# untitled.net
KiCad netlist of a schematic drawn in EAGLE
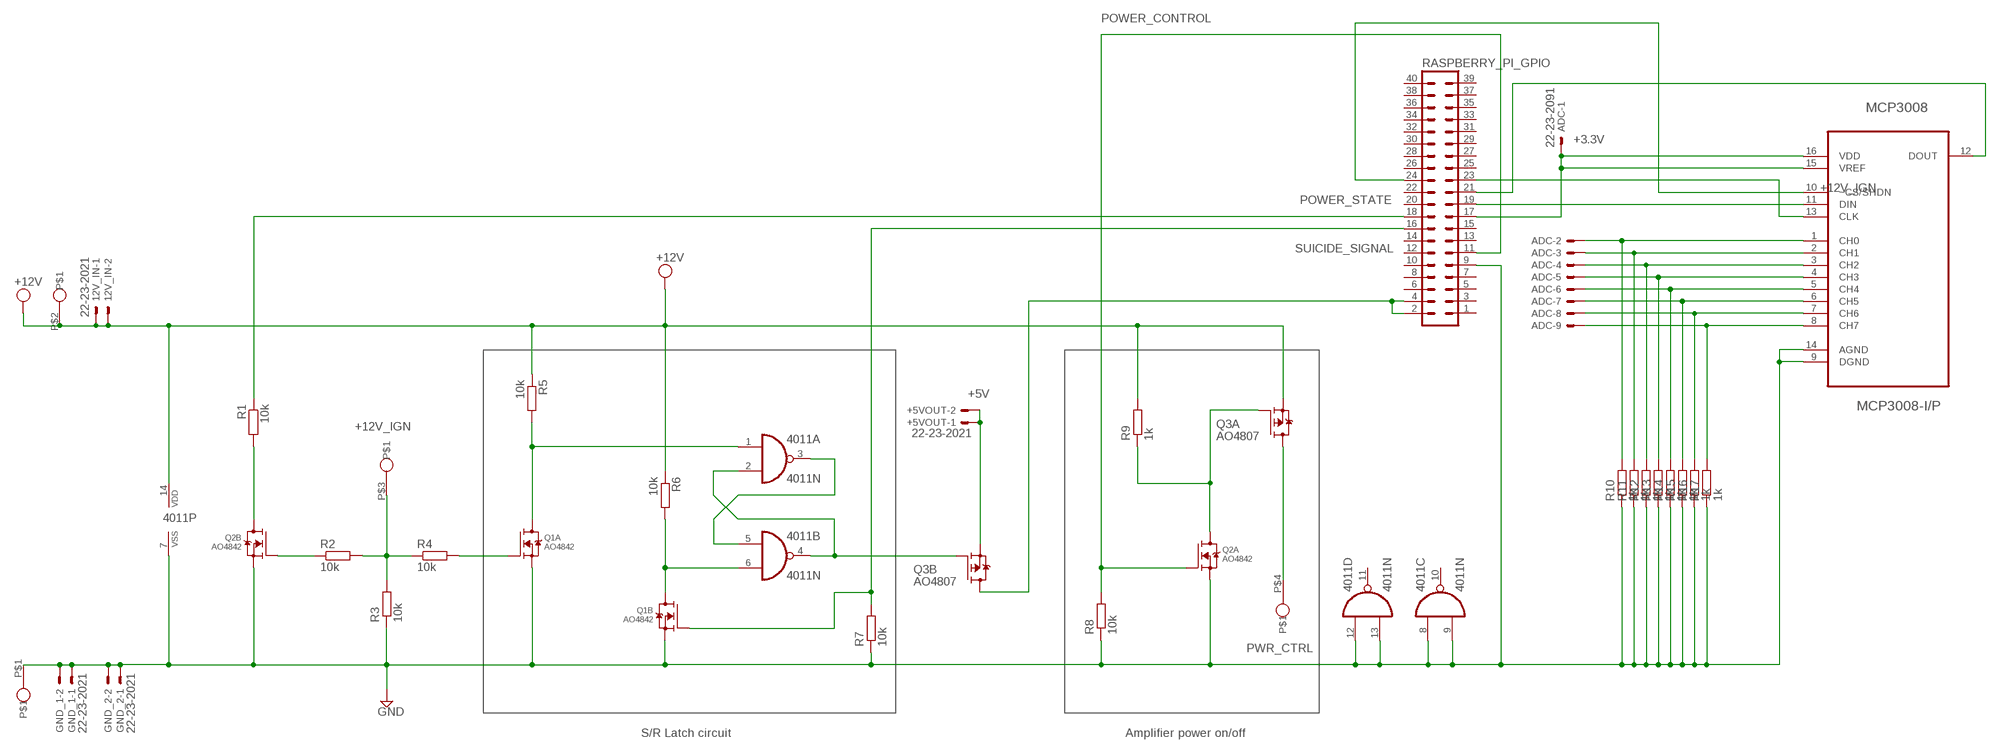
[diagram p0: schematic, sheet 1]

(export (version "E")
  (design (tool "Eeschema 10.0.6"))
  (components
    (comp (ref "+5VOUT")
      (value "22-23-2021")
      (footprint "eagle-import:22-23-2021")
      (fields (field (name "MF") "MOLEX"))
      (libsource (lib "eagle-import") (part "22-23-2021"))
    )
    (comp (ref "12V_IN")
      (value "22-23-2021")
      (footprint "eagle-import:22-23-2021")
      (fields (field (name "MF") "MOLEX"))
      (libsource (lib "eagle-import") (part "22-23-2021"))
    )
    (comp (ref "4011")
      (value "4011N")
      (footprint "eagle-import:DIL14")
      (libsource (lib "eagle-import") (part "4011N"))
    )
    (comp (ref "ADC")
      (value "22-23-2091")
      (footprint "eagle-import:22-23-2091")
      (fields (field (name "MF") "MOLEX"))
      (libsource (lib "eagle-import") (part "22-23-2091"))
    )
    (comp (ref "EXT")
      (value "MKDS3")
      (footprint "eagle-import:MKDS3")
      (libsource (lib "eagle-import") (part "MKDS3"))
    )
    (comp (ref "GND_1")
      (value "22-23-2021")
      (footprint "eagle-import:22-23-2021")
      (fields (field (name "MF") "MOLEX"))
      (libsource (lib "eagle-import") (part "22-23-2021"))
    )
    (comp (ref "GND_2")
      (value "22-23-2021")
      (footprint "eagle-import:22-23-2021")
      (fields (field (name "MF") "MOLEX"))
      (libsource (lib "eagle-import") (part "22-23-2021"))
    )
    (comp (ref "MCP3008")
      (value "MCP3008-I/P")
      (footprint "eagle-import:DIP254P762X432-16")
      (libsource (lib "eagle-import") (part "MCP3008-I/P"))
    )
    (comp (ref "Q1")
      (value "AO4842")
      (footprint "eagle-import:8-SOIC")
      (libsource (lib "eagle-import") (part "AO4842"))
    )
    (comp (ref "Q2")
      (value "AO4842")
      (footprint "eagle-import:8-SOIC")
      (libsource (lib "eagle-import") (part "AO4842"))
    )
    (comp (ref "Q3")
      (value "AO4807")
      (footprint "eagle-import:8-SOIC")
      (libsource (lib "eagle-import") (part "AO4807"))
    )
    (comp (ref "R1")
      (value "10k")
      (footprint "eagle-import:0207_10")
      (libsource (lib "eagle-import") (part "R-EU_0207/10"))
    )
    (comp (ref "R2")
      (value "10k")
      (footprint "eagle-import:0207_10")
      (libsource (lib "eagle-import") (part "R-EU_0207/10"))
    )
    (comp (ref "R3")
      (value "10k")
      (footprint "eagle-import:0207_10")
      (libsource (lib "eagle-import") (part "R-EU_0207/10"))
    )
    (comp (ref "R4")
      (value "10k")
      (footprint "eagle-import:0207_10")
      (libsource (lib "eagle-import") (part "R-EU_0207/10"))
    )
    (comp (ref "R5")
      (value "10k")
      (footprint "eagle-import:0207_10")
      (libsource (lib "eagle-import") (part "R-EU_0207/10"))
    )
    (comp (ref "R6")
      (value "10k")
      (footprint "eagle-import:0207_10")
      (libsource (lib "eagle-import") (part "R-EU_0207/10"))
    )
    (comp (ref "R7")
      (value "10k")
      (footprint "eagle-import:0207_10")
      (libsource (lib "eagle-import") (part "R-EU_0207/10"))
    )
    (comp (ref "R8")
      (value "10k")
      (footprint "eagle-import:0207_10")
      (libsource (lib "eagle-import") (part "R-EU_0207/10"))
    )
    (comp (ref "R9")
      (value "1k")
      (footprint "eagle-import:0207_10")
      (libsource (lib "eagle-import") (part "R-EU_0207/10"))
    )
    (comp (ref "R10")
      (value "1k")
      (footprint "eagle-import:0207_10")
      (libsource (lib "eagle-import") (part "R-EU_0207/10"))
    )
    (comp (ref "R11")
      (value "1k")
      (footprint "eagle-import:0207_10")
      (libsource (lib "eagle-import") (part "R-EU_0207/10"))
    )
    (comp (ref "R12")
      (value "1k")
      (footprint "eagle-import:0207_10")
      (libsource (lib "eagle-import") (part "R-EU_0207/10"))
    )
    (comp (ref "R13")
      (value "1k")
      (footprint "eagle-import:0207_10")
      (libsource (lib "eagle-import") (part "R-EU_0207/10"))
    )
    (comp (ref "R14")
      (value "1k")
      (footprint "eagle-import:0207_10")
      (libsource (lib "eagle-import") (part "R-EU_0207/10"))
    )
    (comp (ref "R15")
      (value "1k")
      (footprint "eagle-import:0207_10")
      (libsource (lib "eagle-import") (part "R-EU_0207/10"))
    )
    (comp (ref "R16")
      (value "1k")
      (footprint "eagle-import:0207_10")
      (libsource (lib "eagle-import") (part "R-EU_0207/10"))
    )
    (comp (ref "R17")
      (value "1k")
      (footprint "eagle-import:0207_10")
      (libsource (lib "eagle-import") (part "R-EU_0207/10"))
    )
    (comp (ref "RASPBERRY_PI_GPIO")
      (value "MA20-2")
      (footprint "eagle-import:MA20-2")
      (libsource (lib "eagle-import") (part "MA20-2"))
    )
  )
  (nets
    (net (code "1") (name "+12V") (class "Default")
      (node (ref "12V_IN") (pin "1") (pinfunction "S_1") (pintype "passive"))
      (node (ref "12V_IN") (pin "2") (pinfunction "S_2") (pintype "passive"))
      (node (ref "4011") (pin "14") (pinfunction "VDD_14") (pintype "power_in"))
      (node (ref "EXT") (pin "P$2") (pinfunction "P$1_P$2") (pintype "bidirectional"))
      (node (ref "Q3") (pin "P$3") (pinfunction "S_P$3") (pintype "passive"))
      (node (ref "R5") (pin "1") (pinfunction "1_1") (pintype "passive"))
      (node (ref "R6") (pin "1") (pinfunction "1_1") (pintype "passive"))
      (node (ref "R9") (pin "2") (pinfunction "2_2") (pintype "passive"))
    )
    (net (code "2") (name "/+3.3V") (class "Default")
      (node (ref "ADC") (pin "1") (pinfunction "S_1") (pintype "passive"))
      (node (ref "MCP3008") (pin "15") (pinfunction "VREF_15") (pintype "power_in"))
      (node (ref "MCP3008") (pin "16") (pinfunction "VDD_16") (pintype "power_in"))
      (node (ref "RASPBERRY_PI_GPIO") (pin "17") (pinfunction "17_17") (pintype "passive"))
    )
    (net (code "3") (name "/+5V") (class "Default")
      (node (ref "+5VOUT") (pin "1") (pinfunction "S_1") (pintype "passive"))
      (node (ref "+5VOUT") (pin "2") (pinfunction "S_2") (pintype "passive"))
      (node (ref "Q3") (pin "P$1") (pinfunction "S_P$1") (pintype "passive"))
    )
    (net (code "4") (name "/+12V_IGN") (class "Default")
      (node (ref "EXT") (pin "P$3") (pinfunction "P$1_P$3") (pintype "bidirectional"))
      (node (ref "R2") (pin "2") (pinfunction "2_2") (pintype "passive"))
      (node (ref "R3") (pin "2") (pinfunction "2_2") (pintype "passive"))
      (node (ref "R4") (pin "1") (pinfunction "1_1") (pintype "passive"))
    )
    (net (code "5") (name "/POWER_CONTROL") (class "Default")
      (node (ref "Q2") (pin "P$4") (pinfunction "G_P$4") (pintype "bidirectional"))
      (node (ref "R8") (pin "2") (pinfunction "2_2") (pintype "passive"))
      (node (ref "RASPBERRY_PI_GPIO") (pin "11") (pinfunction "11_11") (pintype "passive"))
    )
    (net (code "6") (name "/POWER_STATE") (class "Default")
      (node (ref "R1") (pin "1") (pinfunction "1_1") (pintype "passive"))
      (node (ref "RASPBERRY_PI_GPIO") (pin "18") (pinfunction "18_18") (pintype "passive"))
    )
    (net (code "7") (name "/PWR_CTRL") (class "Default")
      (node (ref "EXT") (pin "P$4") (pinfunction "P$1_P$4") (pintype "bidirectional"))
      (node (ref "Q3") (pin "P$5") (pinfunction "D_P$5") (pintype "passive"))
      (node (ref "Q3") (pin "P$6") (pinfunction "D_P$6") (pintype "passive"))
    )
    (net (code "8") (name "/SUICIDE_SIGNAL") (class "Default")
      (node (ref "Q1") (pin "P$2") (pinfunction "G_P$2") (pintype "bidirectional"))
      (node (ref "R7") (pin "2") (pinfunction "2_2") (pintype "passive"))
      (node (ref "RASPBERRY_PI_GPIO") (pin "16") (pinfunction "16_16") (pintype "passive"))
    )
    (net (code "9") (name "GND") (class "Default")
      (node (ref "4011") (pin "12") (pinfunction "I0_12") (pintype "input"))
      (node (ref "4011") (pin "13") (pinfunction "I1_13") (pintype "input"))
      (node (ref "4011") (pin "7") (pinfunction "VSS_7") (pintype "power_in"))
      (node (ref "4011") (pin "8") (pinfunction "I0_8") (pintype "input"))
      (node (ref "4011") (pin "9") (pinfunction "I1_9") (pintype "input"))
      (node (ref "EXT") (pin "P$1") (pinfunction "P$1_P$1") (pintype "bidirectional"))
      (node (ref "GND_1") (pin "1") (pinfunction "S_1") (pintype "passive"))
      (node (ref "GND_1") (pin "2") (pinfunction "S_2") (pintype "passive"))
      (node (ref "GND_2") (pin "1") (pinfunction "S_1") (pintype "passive"))
      (node (ref "GND_2") (pin "2") (pinfunction "S_2") (pintype "passive"))
      (node (ref "MCP3008") (pin "14") (pinfunction "AGND_14") (pintype "passive"))
      (node (ref "MCP3008") (pin "9") (pinfunction "DGND_9") (pintype "passive"))
      (node (ref "Q1") (pin "P$1") (pinfunction "S_P$1") (pintype "bidirectional"))
      (node (ref "Q1") (pin "P$3") (pinfunction "S_P$3") (pintype "bidirectional"))
      (node (ref "Q2") (pin "P$1") (pinfunction "S_P$1") (pintype "bidirectional"))
      (node (ref "Q2") (pin "P$3") (pinfunction "S_P$3") (pintype "bidirectional"))
      (node (ref "R10") (pin "1") (pinfunction "1_1") (pintype "passive"))
      (node (ref "R11") (pin "1") (pinfunction "1_1") (pintype "passive"))
      (node (ref "R12") (pin "1") (pinfunction "1_1") (pintype "passive"))
      (node (ref "R13") (pin "1") (pinfunction "1_1") (pintype "passive"))
      (node (ref "R14") (pin "1") (pinfunction "1_1") (pintype "passive"))
      (node (ref "R15") (pin "1") (pinfunction "1_1") (pintype "passive"))
      (node (ref "R16") (pin "1") (pinfunction "1_1") (pintype "passive"))
      (node (ref "R17") (pin "1") (pinfunction "1_1") (pintype "passive"))
      (node (ref "R3") (pin "1") (pinfunction "1_1") (pintype "passive"))
      (node (ref "R7") (pin "1") (pinfunction "1_1") (pintype "passive"))
      (node (ref "R8") (pin "1") (pinfunction "1_1") (pintype "passive"))
      (node (ref "RASPBERRY_PI_GPIO") (pin "9") (pinfunction "9_9") (pintype "passive"))
    )
    (net (code "10") (name "Net-(4011A-I0)") (class "Default")
      (node (ref "4011") (pin "1") (pinfunction "I0_1") (pintype "input"))
      (node (ref "Q1") (pin "P$5") (pinfunction "D_P$5") (pintype "bidirectional"))
      (node (ref "Q1") (pin "P$6") (pinfunction "D_P$6") (pintype "bidirectional"))
      (node (ref "R5") (pin "2") (pinfunction "2_2") (pintype "passive"))
    )
    (net (code "11") (name "Net-(4011A-I1)") (class "Default")
      (node (ref "4011") (pin "2") (pinfunction "I1_2") (pintype "input"))
      (node (ref "4011") (pin "4") (pinfunction "O_4") (pintype "output"))
      (node (ref "Q3") (pin "P$2") (pinfunction "G_P$2") (pintype "passive"))
    )
    (net (code "12") (name "Net-(4011A-O)") (class "Default")
      (node (ref "4011") (pin "3") (pinfunction "O_3") (pintype "output"))
      (node (ref "4011") (pin "5") (pinfunction "I0_5") (pintype "input"))
    )
    (net (code "13") (name "Net-(4011B-I1)") (class "Default")
      (node (ref "4011") (pin "6") (pinfunction "I1_6") (pintype "input"))
      (node (ref "Q1") (pin "P$7") (pinfunction "D_P$7") (pintype "bidirectional"))
      (node (ref "Q1") (pin "P$8") (pinfunction "D_P$8") (pintype "bidirectional"))
      (node (ref "R6") (pin "2") (pinfunction "2_2") (pintype "passive"))
    )
    (net (code "14") (name "Net-(ADCB-S)") (class "Default")
      (node (ref "ADC") (pin "2") (pinfunction "S_2") (pintype "passive"))
      (node (ref "MCP3008") (pin "1") (pinfunction "CH0_1") (pintype "input"))
      (node (ref "R10") (pin "2") (pinfunction "2_2") (pintype "passive"))
    )
    (net (code "15") (name "Net-(ADCC-S)") (class "Default")
      (node (ref "ADC") (pin "3") (pinfunction "S_3") (pintype "passive"))
      (node (ref "MCP3008") (pin "2") (pinfunction "CH1_2") (pintype "input"))
      (node (ref "R11") (pin "2") (pinfunction "2_2") (pintype "passive"))
    )
    (net (code "16") (name "Net-(ADCD-S)") (class "Default")
      (node (ref "ADC") (pin "4") (pinfunction "S_4") (pintype "passive"))
      (node (ref "MCP3008") (pin "3") (pinfunction "CH2_3") (pintype "input"))
      (node (ref "R12") (pin "2") (pinfunction "2_2") (pintype "passive"))
    )
    (net (code "17") (name "Net-(ADCE-S)") (class "Default")
      (node (ref "ADC") (pin "5") (pinfunction "S_5") (pintype "passive"))
      (node (ref "MCP3008") (pin "4") (pinfunction "CH3_4") (pintype "input"))
      (node (ref "R13") (pin "2") (pinfunction "2_2") (pintype "passive"))
    )
    (net (code "18") (name "Net-(ADCF-S)") (class "Default")
      (node (ref "ADC") (pin "6") (pinfunction "S_6") (pintype "passive"))
      (node (ref "MCP3008") (pin "5") (pinfunction "CH4_5") (pintype "input"))
      (node (ref "R14") (pin "2") (pinfunction "2_2") (pintype "passive"))
    )
    (net (code "19") (name "Net-(ADCG-S)") (class "Default")
      (node (ref "ADC") (pin "7") (pinfunction "S_7") (pintype "passive"))
      (node (ref "MCP3008") (pin "6") (pinfunction "CH5_6") (pintype "input"))
      (node (ref "R15") (pin "2") (pinfunction "2_2") (pintype "passive"))
    )
    (net (code "20") (name "Net-(ADCH-S)") (class "Default")
      (node (ref "ADC") (pin "8") (pinfunction "S_8") (pintype "passive"))
      (node (ref "MCP3008") (pin "7") (pinfunction "CH6_7") (pintype "input"))
      (node (ref "R16") (pin "2") (pinfunction "2_2") (pintype "passive"))
    )
    (net (code "21") (name "Net-(ADCI-S)") (class "Default")
      (node (ref "ADC") (pin "9") (pinfunction "S_9") (pintype "passive"))
      (node (ref "MCP3008") (pin "8") (pinfunction "CH7_8") (pintype "input"))
      (node (ref "R17") (pin "2") (pinfunction "2_2") (pintype "passive"))
    )
    (net (code "22") (name "Net-(MCP3008-CLK)") (class "Default")
      (node (ref "MCP3008") (pin "13") (pinfunction "CLK_13") (pintype "input"))
      (node (ref "RASPBERRY_PI_GPIO") (pin "23") (pinfunction "23_23") (pintype "passive"))
    )
    (net (code "23") (name "Net-(MCP3008-DIN)") (class "Default")
      (node (ref "MCP3008") (pin "11") (pinfunction "DIN_11") (pintype "input"))
      (node (ref "RASPBERRY_PI_GPIO") (pin "19") (pinfunction "19_19") (pintype "passive"))
    )
    (net (code "24") (name "Net-(MCP3008-DOUT)") (class "Default")
      (node (ref "MCP3008") (pin "12") (pinfunction "DOUT_12") (pintype "output"))
      (node (ref "RASPBERRY_PI_GPIO") (pin "21") (pinfunction "21_21") (pintype "passive"))
    )
    (net (code "25") (name "Net-(MCP3008-~{CS{slash}SHDN})") (class "Default")
      (node (ref "MCP3008") (pin "10") (pinfunction "~{CS/SHDN}_10") (pintype "input"))
      (node (ref "RASPBERRY_PI_GPIO") (pin "24") (pinfunction "24_24") (pintype "passive"))
    )
    (net (code "26") (name "Net-(Q1A-G)") (class "Default")
      (node (ref "Q1") (pin "P$4") (pinfunction "G_P$4") (pintype "bidirectional"))
      (node (ref "R4") (pin "2") (pinfunction "2_2") (pintype "passive"))
    )
    (net (code "27") (name "Net-(Q2B-D-PadP$7)") (class "Default")
      (node (ref "Q2") (pin "P$7") (pinfunction "D_P$7") (pintype "bidirectional"))
      (node (ref "Q2") (pin "P$8") (pinfunction "D_P$8") (pintype "bidirectional"))
      (node (ref "R1") (pin "2") (pinfunction "2_2") (pintype "passive"))
    )
    (net (code "28") (name "Net-(Q2B-G)") (class "Default")
      (node (ref "Q2") (pin "P$2") (pinfunction "G_P$2") (pintype "bidirectional"))
      (node (ref "R2") (pin "1") (pinfunction "1_1") (pintype "passive"))
    )
    (net (code "29") (name "Net-(Q3A-G)") (class "Default")
      (node (ref "Q2") (pin "P$5") (pinfunction "D_P$5") (pintype "bidirectional"))
      (node (ref "Q2") (pin "P$6") (pinfunction "D_P$6") (pintype "bidirectional"))
      (node (ref "Q3") (pin "P$4") (pinfunction "G_P$4") (pintype "passive"))
      (node (ref "R9") (pin "1") (pinfunction "1_1") (pintype "passive"))
    )
    (net (code "30") (name "Net-(Q3B-D-PadP$7)") (class "Default")
      (node (ref "Q3") (pin "P$7") (pinfunction "D_P$7") (pintype "passive"))
      (node (ref "Q3") (pin "P$8") (pinfunction "D_P$8") (pintype "passive"))
      (node (ref "RASPBERRY_PI_GPIO") (pin "2") (pinfunction "2_2") (pintype "passive"))
      (node (ref "RASPBERRY_PI_GPIO") (pin "4") (pinfunction "4_4") (pintype "passive"))
    )
    (net (code "31") (name "unconnected-(4011C-O-Pad10)") (class "Default")
      (node (ref "4011") (pin "10") (pinfunction "O_10") (pintype "output"))
    )
    (net (code "32") (name "unconnected-(4011D-O-Pad11)") (class "Default")
      (node (ref "4011") (pin "11") (pinfunction "O_11") (pintype "output"))
    )
    (net (code "33") (name "unconnected-(RASPBERRY_PI_GPIO-Pad1)") (class "Default")
      (node (ref "RASPBERRY_PI_GPIO") (pin "1") (pinfunction "1_1") (pintype "passive"))
    )
    (net (code "34") (name "unconnected-(RASPBERRY_PI_GPIO-Pad3)") (class "Default")
      (node (ref "RASPBERRY_PI_GPIO") (pin "3") (pinfunction "3_3") (pintype "passive"))
    )
    (net (code "35") (name "unconnected-(RASPBERRY_PI_GPIO-Pad5)") (class "Default")
      (node (ref "RASPBERRY_PI_GPIO") (pin "5") (pinfunction "5_5") (pintype "passive"))
    )
    (net (code "36") (name "unconnected-(RASPBERRY_PI_GPIO-Pad6)") (class "Default")
      (node (ref "RASPBERRY_PI_GPIO") (pin "6") (pinfunction "6_6") (pintype "passive"))
    )
    (net (code "37") (name "unconnected-(RASPBERRY_PI_GPIO-Pad7)") (class "Default")
      (node (ref "RASPBERRY_PI_GPIO") (pin "7") (pinfunction "7_7") (pintype "passive"))
    )
    (net (code "38") (name "unconnected-(RASPBERRY_PI_GPIO-Pad8)") (class "Default")
      (node (ref "RASPBERRY_PI_GPIO") (pin "8") (pinfunction "8_8") (pintype "passive"))
    )
    (net (code "39") (name "unconnected-(RASPBERRY_PI_GPIO-Pad10)") (class "Default")
      (node (ref "RASPBERRY_PI_GPIO") (pin "10") (pinfunction "10_10") (pintype "passive"))
    )
    (net (code "40") (name "unconnected-(RASPBERRY_PI_GPIO-Pad12)") (class "Default")
      (node (ref "RASPBERRY_PI_GPIO") (pin "12") (pinfunction "12_12") (pintype "passive"))
    )
    (net (code "41") (name "unconnected-(RASPBERRY_PI_GPIO-Pad13)") (class "Default")
      (node (ref "RASPBERRY_PI_GPIO") (pin "13") (pinfunction "13_13") (pintype "passive"))
    )
    (net (code "42") (name "unconnected-(RASPBERRY_PI_GPIO-Pad14)") (class "Default")
      (node (ref "RASPBERRY_PI_GPIO") (pin "14") (pinfunction "14_14") (pintype "passive"))
    )
    (net (code "43") (name "unconnected-(RASPBERRY_PI_GPIO-Pad15)") (class "Default")
      (node (ref "RASPBERRY_PI_GPIO") (pin "15") (pinfunction "15_15") (pintype "passive"))
    )
    (net (code "44") (name "unconnected-(RASPBERRY_PI_GPIO-Pad20)") (class "Default")
      (node (ref "RASPBERRY_PI_GPIO") (pin "20") (pinfunction "20_20") (pintype "passive"))
    )
    (net (code "45") (name "unconnected-(RASPBERRY_PI_GPIO-Pad22)") (class "Default")
      (node (ref "RASPBERRY_PI_GPIO") (pin "22") (pinfunction "22_22") (pintype "passive"))
    )
    (net (code "46") (name "unconnected-(RASPBERRY_PI_GPIO-Pad25)") (class "Default")
      (node (ref "RASPBERRY_PI_GPIO") (pin "25") (pinfunction "25_25") (pintype "passive"))
    )
    (net (code "47") (name "unconnected-(RASPBERRY_PI_GPIO-Pad26)") (class "Default")
      (node (ref "RASPBERRY_PI_GPIO") (pin "26") (pinfunction "26_26") (pintype "passive"))
    )
    (net (code "48") (name "unconnected-(RASPBERRY_PI_GPIO-Pad27)") (class "Default")
      (node (ref "RASPBERRY_PI_GPIO") (pin "27") (pinfunction "27_27") (pintype "passive"))
    )
    (net (code "49") (name "unconnected-(RASPBERRY_PI_GPIO-Pad28)") (class "Default")
      (node (ref "RASPBERRY_PI_GPIO") (pin "28") (pinfunction "28_28") (pintype "passive"))
    )
    (net (code "50") (name "unconnected-(RASPBERRY_PI_GPIO-Pad29)") (class "Default")
      (node (ref "RASPBERRY_PI_GPIO") (pin "29") (pinfunction "29_29") (pintype "passive"))
    )
    (net (code "51") (name "unconnected-(RASPBERRY_PI_GPIO-Pad30)") (class "Default")
      (node (ref "RASPBERRY_PI_GPIO") (pin "30") (pinfunction "30_30") (pintype "passive"))
    )
    (net (code "52") (name "unconnected-(RASPBERRY_PI_GPIO-Pad31)") (class "Default")
      (node (ref "RASPBERRY_PI_GPIO") (pin "31") (pinfunction "31_31") (pintype "passive"))
    )
    (net (code "53") (name "unconnected-(RASPBERRY_PI_GPIO-Pad32)") (class "Default")
      (node (ref "RASPBERRY_PI_GPIO") (pin "32") (pinfunction "32_32") (pintype "passive"))
    )
    (net (code "54") (name "unconnected-(RASPBERRY_PI_GPIO-Pad33)") (class "Default")
      (node (ref "RASPBERRY_PI_GPIO") (pin "33") (pinfunction "33_33") (pintype "passive"))
    )
    (net (code "55") (name "unconnected-(RASPBERRY_PI_GPIO-Pad34)") (class "Default")
      (node (ref "RASPBERRY_PI_GPIO") (pin "34") (pinfunction "34_34") (pintype "passive"))
    )
    (net (code "56") (name "unconnected-(RASPBERRY_PI_GPIO-Pad35)") (class "Default")
      (node (ref "RASPBERRY_PI_GPIO") (pin "35") (pinfunction "35_35") (pintype "passive"))
    )
    (net (code "57") (name "unconnected-(RASPBERRY_PI_GPIO-Pad36)") (class "Default")
      (node (ref "RASPBERRY_PI_GPIO") (pin "36") (pinfunction "36_36") (pintype "passive"))
    )
    (net (code "58") (name "unconnected-(RASPBERRY_PI_GPIO-Pad37)") (class "Default")
      (node (ref "RASPBERRY_PI_GPIO") (pin "37") (pinfunction "37_37") (pintype "passive"))
    )
    (net (code "59") (name "unconnected-(RASPBERRY_PI_GPIO-Pad38)") (class "Default")
      (node (ref "RASPBERRY_PI_GPIO") (pin "38") (pinfunction "38_38") (pintype "passive"))
    )
    (net (code "60") (name "unconnected-(RASPBERRY_PI_GPIO-Pad39)") (class "Default")
      (node (ref "RASPBERRY_PI_GPIO") (pin "39") (pinfunction "39_39") (pintype "passive"))
    )
    (net (code "61") (name "unconnected-(RASPBERRY_PI_GPIO-Pad40)") (class "Default")
      (node (ref "RASPBERRY_PI_GPIO") (pin "40") (pinfunction "40_40") (pintype "passive"))
    )
  )
)
